# PULSE.net
KiCad netlist of a schematic drawn in Altium Designer
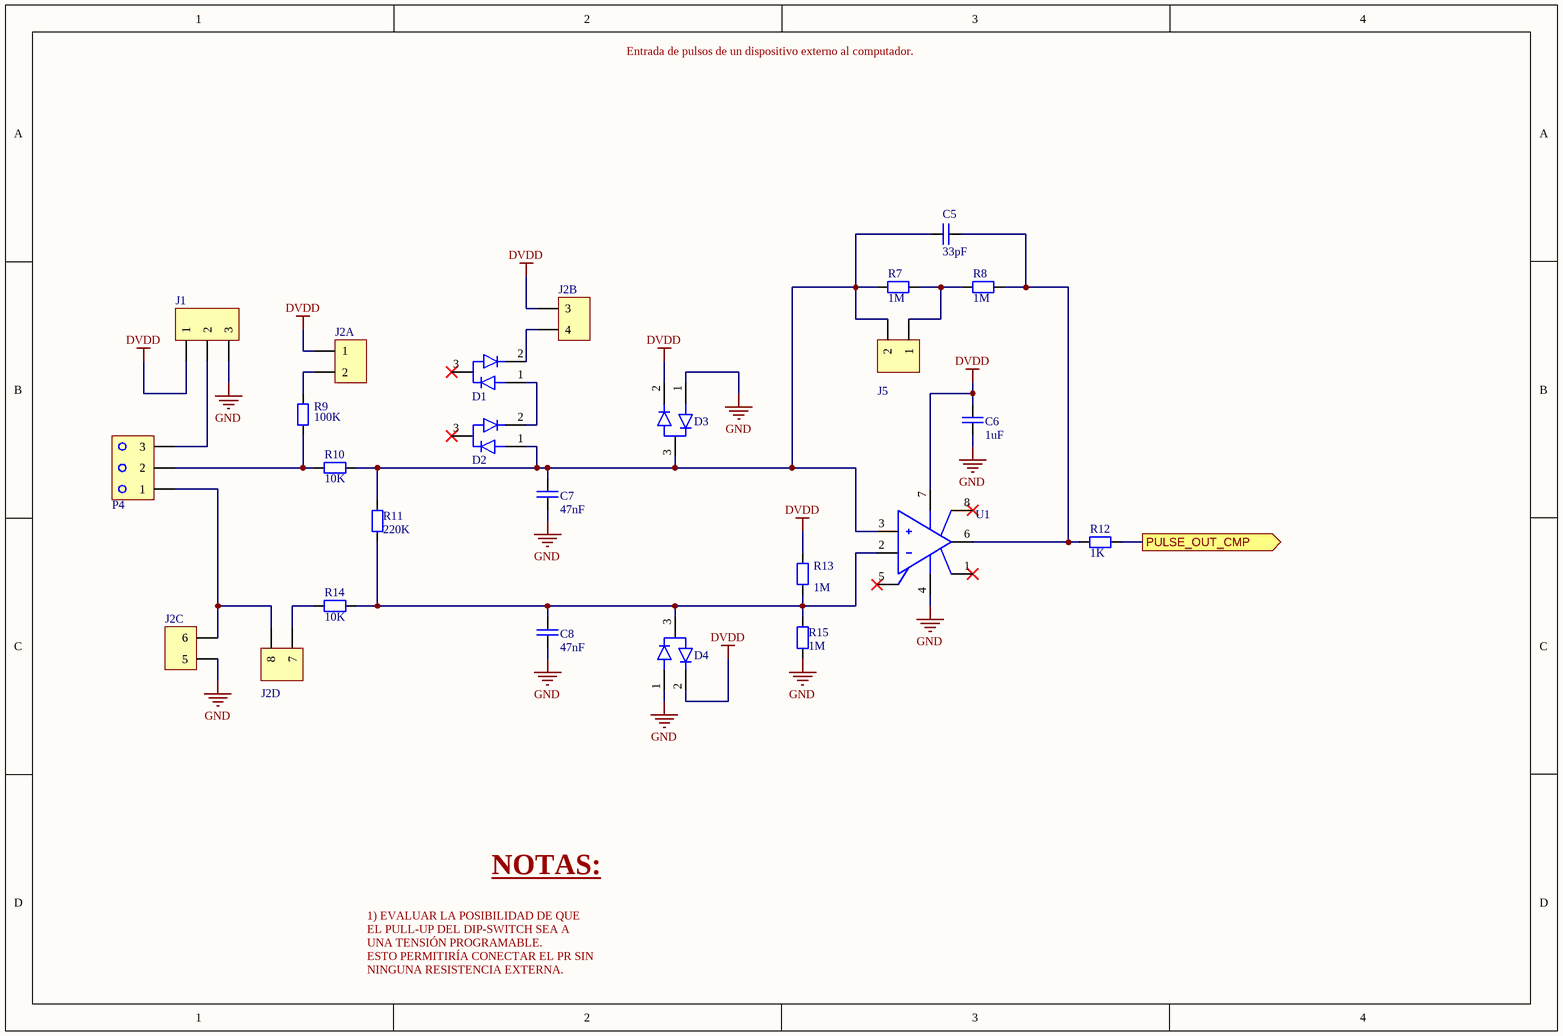
[diagram p0: PULSE.SchDoc]

(export (version "E")
  (design (tool "Eeschema 10.0.6"))
  (components
    (comp (ref "C5")
      (value "33pF")
      (footprint "CAP_SM0805_YAGEOCC2_N")
      (description "CAP 33pF SM0805 NPO 50V YAGEO CC2")
      (fields
        (field (name "MANUFACTURER") "Yageo")
        (field (name "MANUFACTURER PART NUMBER") "CC0805JRNPO9BN330")
      )
      (libsource (lib "Yageo") (part "CC0805JRNPO9BN330"))
    )
    (comp (ref "C6")
      (value "1uF")
      (footprint "CAP_SM0805_YAGEOCC2_N")
      (description "CAP 1uF SM0805 X7R 25V YAGEO CC2")
      (fields
        (field (name "MANUFACTURER") "Yageo")
        (field (name "MANUFACTURER PART NUMBER") "CC0805KKX7R8BB105")
      )
      (libsource (lib "Yageo") (part "CC0805KKX7R8BB105"))
    )
    (comp (ref "C7")
      (value "47nF")
      (footprint "CAP_SM0805_YAGEOCC2_N")
      (description "CAP 47nF SM0805 X7R 25V YAGEO CC2")
      (fields
        (field (name "MANUFACTURER") "Yageo")
        (field (name "MANUFACTURER PART NUMBER") "CC0805KRX7R8BB473")
      )
      (libsource (lib "Yageo") (part "CC0805KRX7R8BB473"))
    )
    (comp (ref "C8")
      (value "47nF")
      (footprint "CAP_SM0805_YAGEOCC2_N")
      (description "CAP 47nF SM0805 X7R 25V YAGEO CC2")
      (fields
        (field (name "MANUFACTURER") "Yageo")
        (field (name "MANUFACTURER PART NUMBER") "CC0805KRX7R8BB473")
      )
      (libsource (lib "Yageo") (part "CC0805KRX7R8BB473"))
    )
    (comp (ref "D1")
      (value "BAV23S")
      (footprint "BAV23S")
      (description "DIODE ARRAY GP 250V 200MA SOT23")
      (fields (field (name "MANUFACTURER") "onsemi"))
      (libsource (lib "diode") (part "BAV23S"))
    )
    (comp (ref "D2")
      (value "BAV23S")
      (footprint "BAV23S")
      (description "DIODE ARRAY GP 250V 200MA SOT23")
      (fields (field (name "MANUFACTURER") "onsemi"))
      (libsource (lib "diode") (part "BAV23S"))
    )
    (comp (ref "D3")
      (value "BAV23S")
      (footprint "BAV23S")
      (description "DIODE ARRAY GP 250V 200MA SOT23")
      (fields (field (name "MANUFACTURER") "onsemi"))
      (libsource (lib "diode") (part "BAV23S"))
    )
    (comp (ref "D4")
      (value "BAV23S")
      (footprint "BAV23S")
      (description "DIODE ARRAY GP 250V 200MA SOT23")
      (fields (field (name "MANUFACTURER") "onsemi"))
      (libsource (lib "diode") (part "BAV23S"))
    )
    (comp (ref "J1")
      (value "~")
      (footprint "HEADER PIN 1X3")
      (description "1 x 3 - Cuttable - true hole  2.54mm - Pb free")
      (fields
        (field (name "MANUFACTURER") "Amphenol ICC")
        (field (name "MANUFACTURER PART NUMBER") "54101-T06-00")
      )
      (libsource (lib "header_pin") (part "54101-T0600LF-03"))
    )
    (comp (ref "J2")
      (value "Usar equivalente")
      (footprint "HEADER PIN 2X4")
      (description "2 x 4  - true hole  2.54mm")
      (fields
        (field (name "MANUFACTURER") "Amphenol ICC")
        (field (name "MANUFACTURER PARTNUMBER") "54102-T0604LF")
      )
      (libsource (lib "") (part "54102-T0604LF-JUMPER_1"))
    )
    (comp (ref "J5")
      (value "Usar Equivalente")
      (footprint "HEADER PIN 1X2")
      (description "1 x 2 - true hole  2.54mm - Pb free")
      (fields
        (field (name "MANUFACTURER") "Amphenol ICC")
        (field (name "MANUFACTURER PART NUMBER") "54101-T0602LF")
      )
      (libsource (lib "header_pin") (part "54101-T0602LF"))
    )
    (comp (ref "P4")
      (value "WJ15EDGVC-3.81-3P")
      (footprint "HEADER PLUG 3")
      (description "TERM BLOK FEMALE 1X3 3.81MM")
      (fields (field (name "MANUFACTURER") "Ningbo Kangnex Elec"))
      (libsource (lib "plug") (part "WJ15EDGVC-3.81-3P"))
    )
    (comp (ref "R7")
      (value "1M")
      (footprint "RES_SM0805_YAGEORC_N")
      (description "RES 1M SM0805 YAGEO RC_L")
      (fields
        (field (name "MANUFACTURER") "Yageo")
        (field (name "MANUFACTURER PART NUMBER") "RC0805FR-071ML")
      )
      (libsource (lib "Yageo") (part "RC0805FR-071ML"))
    )
    (comp (ref "R8")
      (value "1M")
      (footprint "RES_SM0805_YAGEORC_N")
      (description "RES 1M SM0805 YAGEO RC_L")
      (fields
        (field (name "MANUFACTURER") "Yageo")
        (field (name "MANUFACTURER PART NUMBER") "RC0805FR-071ML")
      )
      (libsource (lib "Yageo") (part "RC0805FR-071ML"))
    )
    (comp (ref "R9")
      (value "100K")
      (footprint "RES_SM0805_YAGEORC_N")
      (description "RES 100K SM0805 YAGEO RC_L")
      (fields
        (field (name "MANUFACTURER") "Yageo")
        (field (name "MANUFACTURER PART NUMBER") "RC0805FR-07100KL")
      )
      (libsource (lib "Yageo") (part "RC0805FR-07100KL"))
    )
    (comp (ref "R10")
      (value "10K")
      (footprint "RES_SM0805_YAGEORC_N")
      (description "RES 10K SM0805 YAGEO RC_L")
      (fields
        (field (name "MANUFACTURER") "Yageo")
        (field (name "MANUFACTURER PART NUMBER") "RC0805FR-0710KL")
      )
      (libsource (lib "Yageo") (part "RC0805FR-0710KL"))
    )
    (comp (ref "R11")
      (value "220K")
      (footprint "RES_SM0805_YAGEORC_N")
      (description "RES 220K SM0805 YAGEO RC_L")
      (fields
        (field (name "MANUFACTURER") "Yageo")
        (field (name "MANUFACTURER PART NUMBER") "RC0805FR-07220KL")
      )
      (libsource (lib "Yageo") (part "RC0805FR-07220KL"))
    )
    (comp (ref "R12")
      (value "1K")
      (footprint "RES_SM0805_YAGEORC_N")
      (description "RES 1K SM0805 YAGEO RC_L")
      (fields
        (field (name "MANUFACTURER") "Yageo")
        (field (name "MANUFACTURER PART NUMBER") "RC0805FR-071KL")
      )
      (libsource (lib "Yageo") (part "RC0805FR-071KL"))
    )
    (comp (ref "R13")
      (value "1M")
      (footprint "RES_SM0805_YAGEORC_N")
      (description "RES 1M SM0805 YAGEO RC_L")
      (fields
        (field (name "MANUFACTURER") "Yageo")
        (field (name "MANUFACTURER PART NUMBER") "RC0805FR-071ML")
      )
      (libsource (lib "") (part "RC0805FR-071ML_1"))
    )
    (comp (ref "R14")
      (value "10K")
      (footprint "RES_SM0805_YAGEORC_N")
      (description "RES 10K SM0805 YAGEO RC_L")
      (fields
        (field (name "MANUFACTURER") "Yageo")
        (field (name "MANUFACTURER PART NUMBER") "RC0805FR-0710KL")
      )
      (libsource (lib "Yageo") (part "RC0805FR-0710KL"))
    )
    (comp (ref "R15")
      (value "1M")
      (footprint "RES_SM0805_YAGEORC_N")
      (description "RES 1M SM0805 YAGEO RC_L")
      (fields
        (field (name "MANUFACTURER") "Yageo")
        (field (name "MANUFACTURER PART NUMBER") "RC0805FR-071ML")
      )
      (libsource (lib "") (part "RC0805FR-071ML_1"))
    )
    (comp (ref "U1")
      (value "MCP6541")
      (footprint "MCP6541-E/SN")
      (description "IC COMP PP I/O SNGL 1.6V 8SOIC")
      (fields
        (field (name "MANUFACTURER") "Microchip Tech")
        (field (name "MANUFACTURER PART NUMBER") "MCP6541-E/SN")
      )
      (libsource (lib "OP_Amps") (part "MCP6541-E/SN"))
    )
  )
  (nets
    (net (code "1") (name "/PULSE_OUT_CMP") (class "Default")
      (node (ref "R12") (pin "2") (pintype "passive"))
    )
    (net (code "2") (name "DVDD") (class "Default")
      (node (ref "C6") (pin "1") (pintype "passive"))
      (node (ref "D3") (pin "2") (pinfunction "2_2") (pintype "passive"))
      (node (ref "D4") (pin "2") (pinfunction "2_2") (pintype "passive"))
      (node (ref "J1") (pin "1") (pinfunction "1_1") (pintype "passive"))
      (node (ref "J2") (pin "1") (pinfunction "1_1") (pintype "passive"))
      (node (ref "J2") (pin "3") (pinfunction "3_3") (pintype "passive"))
      (node (ref "R13") (pin "2") (pintype "passive"))
      (node (ref "U1") (pin "7") (pinfunction "V+_7") (pintype "power_in"))
    )
    (net (code "3") (name "GND") (class "Default")
      (node (ref "C6") (pin "2") (pintype "passive"))
      (node (ref "C7") (pin "2") (pintype "passive"))
      (node (ref "C8") (pin "2") (pintype "passive"))
      (node (ref "D3") (pin "1") (pinfunction "1_1") (pintype "passive"))
      (node (ref "D4") (pin "1") (pinfunction "1_1") (pintype "passive"))
      (node (ref "J1") (pin "3") (pinfunction "3_3") (pintype "passive"))
      (node (ref "J2") (pin "5") (pinfunction "5_5") (pintype "passive"))
      (node (ref "R15") (pin "1") (pintype "passive"))
      (node (ref "U1") (pin "4") (pinfunction "V-_4") (pintype "power_in"))
    )
    (net (code "4") (name "Net-(D1-Pad1)") (class "Default")
      (node (ref "D1") (pin "1") (pinfunction "1_1") (pintype "passive"))
      (node (ref "D2") (pin "2") (pinfunction "2_2") (pintype "passive"))
    )
    (net (code "5") (name "Net-(D1-Pad2)") (class "Default")
      (node (ref "D1") (pin "2") (pinfunction "2_2") (pintype "passive"))
      (node (ref "J2") (pin "4") (pinfunction "4_4") (pintype "passive"))
    )
    (net (code "6") (name "Net-(J1-Pad2)") (class "Default")
      (node (ref "J1") (pin "2") (pinfunction "2_2") (pintype "passive"))
      (node (ref "P4") (pin "3") (pinfunction "3_3") (pintype "passive"))
    )
    (net (code "7") (name "Net-(J2-Pad2)") (class "Default")
      (node (ref "J2") (pin "2") (pinfunction "2_2") (pintype "passive"))
      (node (ref "R9") (pin "2") (pintype "passive"))
    )
    (net (code "8") (name "Net-(J2-Pad6)") (class "Default")
      (node (ref "J2") (pin "6") (pinfunction "6_6") (pintype "passive"))
      (node (ref "J2") (pin "8") (pinfunction "8_8") (pintype "passive"))
      (node (ref "P4") (pin "1") (pinfunction "1_1") (pintype "passive"))
    )
    (net (code "9") (name "Net-(J2-Pad7)") (class "Default")
      (node (ref "J2") (pin "7") (pinfunction "7_7") (pintype "passive"))
      (node (ref "R14") (pin "1") (pintype "passive"))
    )
    (net (code "10") (name "Net-(J5-Pad1)") (class "Default")
      (node (ref "J5") (pin "1") (pinfunction "1_1") (pintype "passive"))
      (node (ref "R7") (pin "2") (pintype "passive"))
      (node (ref "R8") (pin "1") (pintype "passive"))
    )
    (net (code "11") (name "Net-(P4-Pad2)") (class "Default")
      (node (ref "P4") (pin "2") (pinfunction "2_2") (pintype "passive"))
      (node (ref "R10") (pin "1") (pintype "passive"))
      (node (ref "R9") (pin "1") (pintype "passive"))
    )
    (net (code "12") (name "Net-(U1-IN+)") (class "Default")
      (node (ref "C5") (pin "1") (pintype "passive"))
      (node (ref "C7") (pin "1") (pintype "passive"))
      (node (ref "D2") (pin "1") (pinfunction "1_1") (pintype "passive"))
      (node (ref "D3") (pin "3") (pinfunction "3_3") (pintype "passive"))
      (node (ref "J5") (pin "2") (pinfunction "2_2") (pintype "passive"))
      (node (ref "R10") (pin "2") (pintype "passive"))
      (node (ref "R11") (pin "2") (pintype "passive"))
      (node (ref "R7") (pin "1") (pintype "passive"))
      (node (ref "U1") (pin "3") (pinfunction "IN+_3") (pintype "passive"))
    )
    (net (code "13") (name "Net-(U1-IN-)") (class "Default")
      (node (ref "C8") (pin "1") (pintype "passive"))
      (node (ref "D4") (pin "3") (pinfunction "3_3") (pintype "passive"))
      (node (ref "R11") (pin "1") (pintype "passive"))
      (node (ref "R13") (pin "1") (pintype "passive"))
      (node (ref "R14") (pin "2") (pintype "passive"))
      (node (ref "R15") (pin "2") (pintype "passive"))
      (node (ref "U1") (pin "2") (pinfunction "IN-_2") (pintype "passive"))
    )
    (net (code "14") (name "Net-(U1-OUT)") (class "Default")
      (node (ref "C5") (pin "2") (pintype "passive"))
      (node (ref "R12") (pin "1") (pintype "passive"))
      (node (ref "R8") (pin "2") (pintype "passive"))
      (node (ref "U1") (pin "6") (pinfunction "OUT_6") (pintype "passive"))
    )
    (net (code "15") (name "unconnected-(D1-Pad3)") (class "Default")
      (node (ref "D1") (pin "3") (pinfunction "3_3") (pintype "passive+no_connect"))
    )
    (net (code "16") (name "unconnected-(D2-Pad3)") (class "Default")
      (node (ref "D2") (pin "3") (pinfunction "3_3") (pintype "passive+no_connect"))
    )
    (net (code "17") (name "unconnected-(U1-OS_NUL-Pad1)") (class "Default")
      (node (ref "U1") (pin "1") (pinfunction "OS_NUL_1") (pintype "passive+no_connect"))
    )
    (net (code "18") (name "unconnected-(U1-OS_NUL-Pad5)") (class "Default")
      (node (ref "U1") (pin "5") (pinfunction "OS_NUL_5") (pintype "passive+no_connect"))
    )
    (net (code "19") (name "unconnected-(U1-TAB-Pad8)") (class "Default")
      (node (ref "U1") (pin "8") (pinfunction "TAB_8") (pintype "passive+no_connect"))
    )
  )
)
